# Master_flying_pcb_v1.net
KiCad netlist of a schematic drawn in Altium Designer
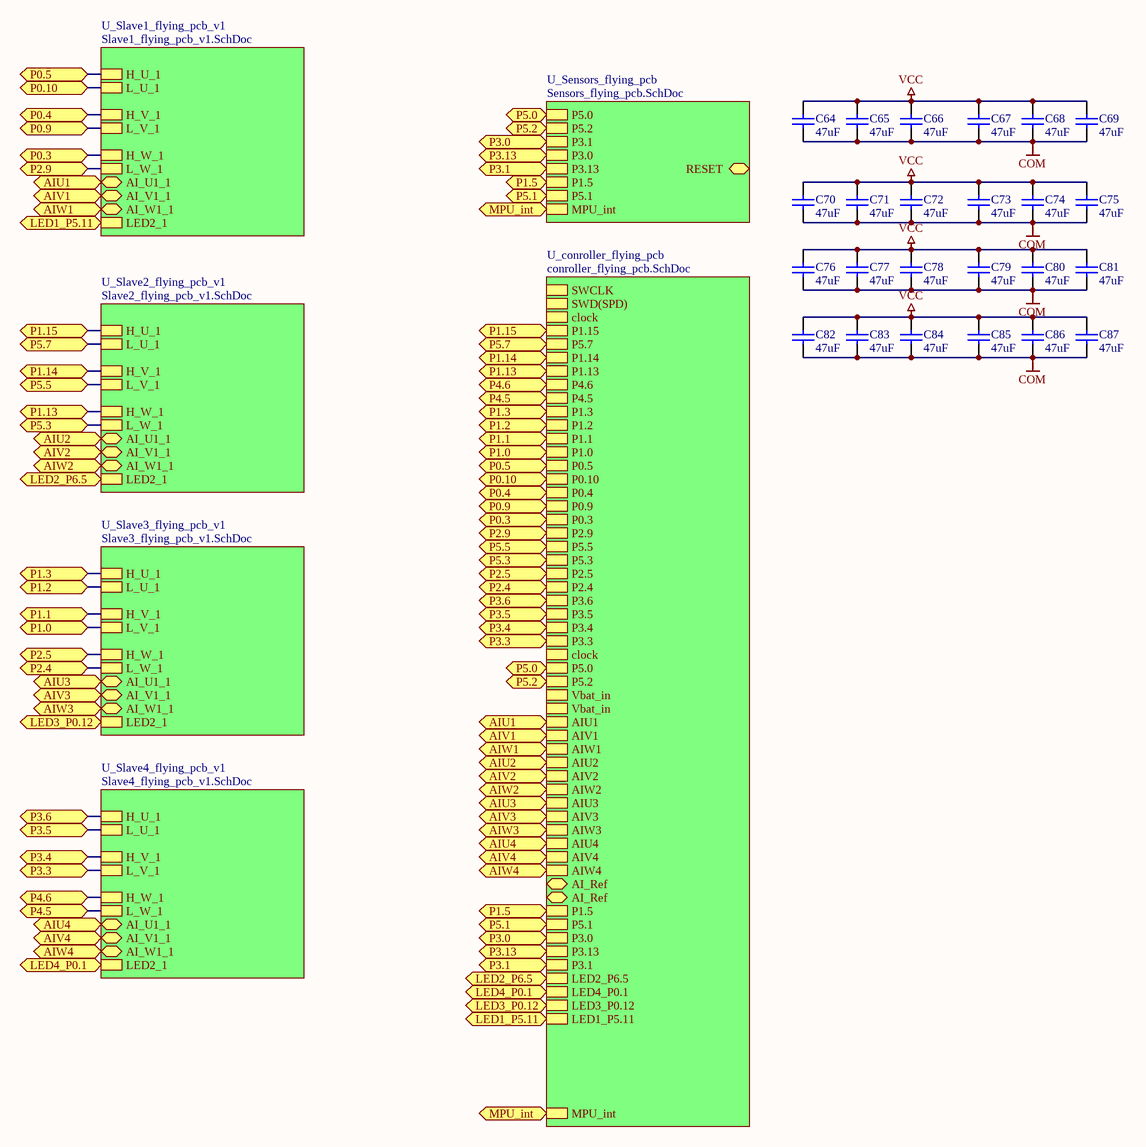
[diagram p0: Master_flying_pcb_v1.SchDoc]

(export (version "E")
  (design (tool "Eeschema 10.0.6"))
  (components
    (comp (ref "C64") (value "47uF") (footprint "_0805") (libsource (lib "Capacitors$") (part "Cap_128")))
    (comp (ref "C65") (value "47uF") (footprint "_0805") (libsource (lib "Capacitors$") (part "Cap_128")))
    (comp (ref "C66") (value "47uF") (footprint "_0805") (libsource (lib "Capacitors$") (part "Cap_128")))
    (comp (ref "C67") (value "47uF") (footprint "_0805") (libsource (lib "Capacitors$") (part "Cap_128")))
    (comp (ref "C68") (value "47uF") (footprint "_0805") (libsource (lib "Capacitors$") (part "Cap_128")))
    (comp (ref "C69") (value "47uF") (footprint "_0805") (libsource (lib "Capacitors$") (part "Cap_128")))
    (comp (ref "C70") (value "47uF") (footprint "_0805") (libsource (lib "Capacitors$") (part "Cap_128")))
    (comp (ref "C71") (value "47uF") (footprint "_0805") (libsource (lib "Capacitors$") (part "Cap_128")))
    (comp (ref "C72") (value "47uF") (footprint "_0805") (libsource (lib "Capacitors$") (part "Cap_128")))
    (comp (ref "C73") (value "47uF") (footprint "_0805") (libsource (lib "Capacitors$") (part "Cap_128")))
    (comp (ref "C74") (value "47uF") (footprint "_0805") (libsource (lib "Capacitors$") (part "Cap_128")))
    (comp (ref "C75") (value "47uF") (footprint "_0805") (libsource (lib "Capacitors$") (part "Cap_128")))
    (comp (ref "C76") (value "47uF") (footprint "_0805") (libsource (lib "Capacitors$") (part "Cap_128")))
    (comp (ref "C77") (value "47uF") (footprint "_0805") (libsource (lib "Capacitors$") (part "Cap_128")))
    (comp (ref "C78") (value "47uF") (footprint "_0805") (libsource (lib "Capacitors$") (part "Cap_128")))
    (comp (ref "C79") (value "47uF") (footprint "_0805") (libsource (lib "Capacitors$") (part "Cap_128")))
    (comp (ref "C80") (value "47uF") (footprint "_0805") (libsource (lib "Capacitors$") (part "Cap_128")))
    (comp (ref "C81") (value "47uF") (footprint "_0805") (libsource (lib "Capacitors$") (part "Cap_128")))
    (comp (ref "C82") (value "47uF") (footprint "_0805") (libsource (lib "Capacitors$") (part "Cap_128")))
    (comp (ref "C83") (value "47uF") (footprint "_0805") (libsource (lib "Capacitors$") (part "Cap_128")))
    (comp (ref "C84") (value "47uF") (footprint "_0805") (libsource (lib "Capacitors$") (part "Cap_128")))
    (comp (ref "C85") (value "47uF") (footprint "_0805") (libsource (lib "Capacitors$") (part "Cap_128")))
    (comp (ref "C86") (value "47uF") (footprint "_0805") (libsource (lib "Capacitors$") (part "Cap_128")))
    (comp (ref "C87") (value "47uF") (footprint "_0805") (libsource (lib "Capacitors$") (part "Cap_128")))
  )
  (nets
    (net (code "58") (name "COM") (class "Default")
      (node (ref "C64") (pin "1") (pinfunction "1_1") (pintype "passive"))
      (node (ref "C65") (pin "1") (pinfunction "1_1") (pintype "passive"))
      (node (ref "C66") (pin "1") (pinfunction "1_1") (pintype "passive"))
      (node (ref "C67") (pin "1") (pinfunction "1_1") (pintype "passive"))
      (node (ref "C68") (pin "1") (pinfunction "1_1") (pintype "passive"))
      (node (ref "C69") (pin "1") (pinfunction "1_1") (pintype "passive"))
      (node (ref "C70") (pin "1") (pinfunction "1_1") (pintype "passive"))
      (node (ref "C71") (pin "1") (pinfunction "1_1") (pintype "passive"))
      (node (ref "C72") (pin "1") (pinfunction "1_1") (pintype "passive"))
      (node (ref "C73") (pin "1") (pinfunction "1_1") (pintype "passive"))
      (node (ref "C74") (pin "1") (pinfunction "1_1") (pintype "passive"))
      (node (ref "C75") (pin "1") (pinfunction "1_1") (pintype "passive"))
      (node (ref "C76") (pin "1") (pinfunction "1_1") (pintype "passive"))
      (node (ref "C77") (pin "1") (pinfunction "1_1") (pintype "passive"))
      (node (ref "C78") (pin "1") (pinfunction "1_1") (pintype "passive"))
      (node (ref "C79") (pin "1") (pinfunction "1_1") (pintype "passive"))
      (node (ref "C80") (pin "1") (pinfunction "1_1") (pintype "passive"))
      (node (ref "C81") (pin "1") (pinfunction "1_1") (pintype "passive"))
      (node (ref "C82") (pin "1") (pinfunction "1_1") (pintype "passive"))
      (node (ref "C83") (pin "1") (pinfunction "1_1") (pintype "passive"))
      (node (ref "C84") (pin "1") (pinfunction "1_1") (pintype "passive"))
      (node (ref "C85") (pin "1") (pinfunction "1_1") (pintype "passive"))
      (node (ref "C86") (pin "1") (pinfunction "1_1") (pintype "passive"))
      (node (ref "C87") (pin "1") (pinfunction "1_1") (pintype "passive"))
    )
    (net (code "59") (name "VCC") (class "Default")
      (node (ref "C64") (pin "2") (pinfunction "2_2") (pintype "passive"))
      (node (ref "C65") (pin "2") (pinfunction "2_2") (pintype "passive"))
      (node (ref "C66") (pin "2") (pinfunction "2_2") (pintype "passive"))
      (node (ref "C67") (pin "2") (pinfunction "2_2") (pintype "passive"))
      (node (ref "C68") (pin "2") (pinfunction "2_2") (pintype "passive"))
      (node (ref "C69") (pin "2") (pinfunction "2_2") (pintype "passive"))
      (node (ref "C70") (pin "2") (pinfunction "2_2") (pintype "passive"))
      (node (ref "C71") (pin "2") (pinfunction "2_2") (pintype "passive"))
      (node (ref "C72") (pin "2") (pinfunction "2_2") (pintype "passive"))
      (node (ref "C73") (pin "2") (pinfunction "2_2") (pintype "passive"))
      (node (ref "C74") (pin "2") (pinfunction "2_2") (pintype "passive"))
      (node (ref "C75") (pin "2") (pinfunction "2_2") (pintype "passive"))
      (node (ref "C76") (pin "2") (pinfunction "2_2") (pintype "passive"))
      (node (ref "C77") (pin "2") (pinfunction "2_2") (pintype "passive"))
      (node (ref "C78") (pin "2") (pinfunction "2_2") (pintype "passive"))
      (node (ref "C79") (pin "2") (pinfunction "2_2") (pintype "passive"))
      (node (ref "C80") (pin "2") (pinfunction "2_2") (pintype "passive"))
      (node (ref "C81") (pin "2") (pinfunction "2_2") (pintype "passive"))
      (node (ref "C82") (pin "2") (pinfunction "2_2") (pintype "passive"))
      (node (ref "C83") (pin "2") (pinfunction "2_2") (pintype "passive"))
      (node (ref "C84") (pin "2") (pinfunction "2_2") (pintype "passive"))
      (node (ref "C85") (pin "2") (pinfunction "2_2") (pintype "passive"))
      (node (ref "C86") (pin "2") (pinfunction "2_2") (pintype "passive"))
      (node (ref "C87") (pin "2") (pinfunction "2_2") (pintype "passive"))
    )
  )
)
